# Own_18650_Board_v1_3_Final_AR.net
KiCad netlist of a schematic drawn in EAGLE
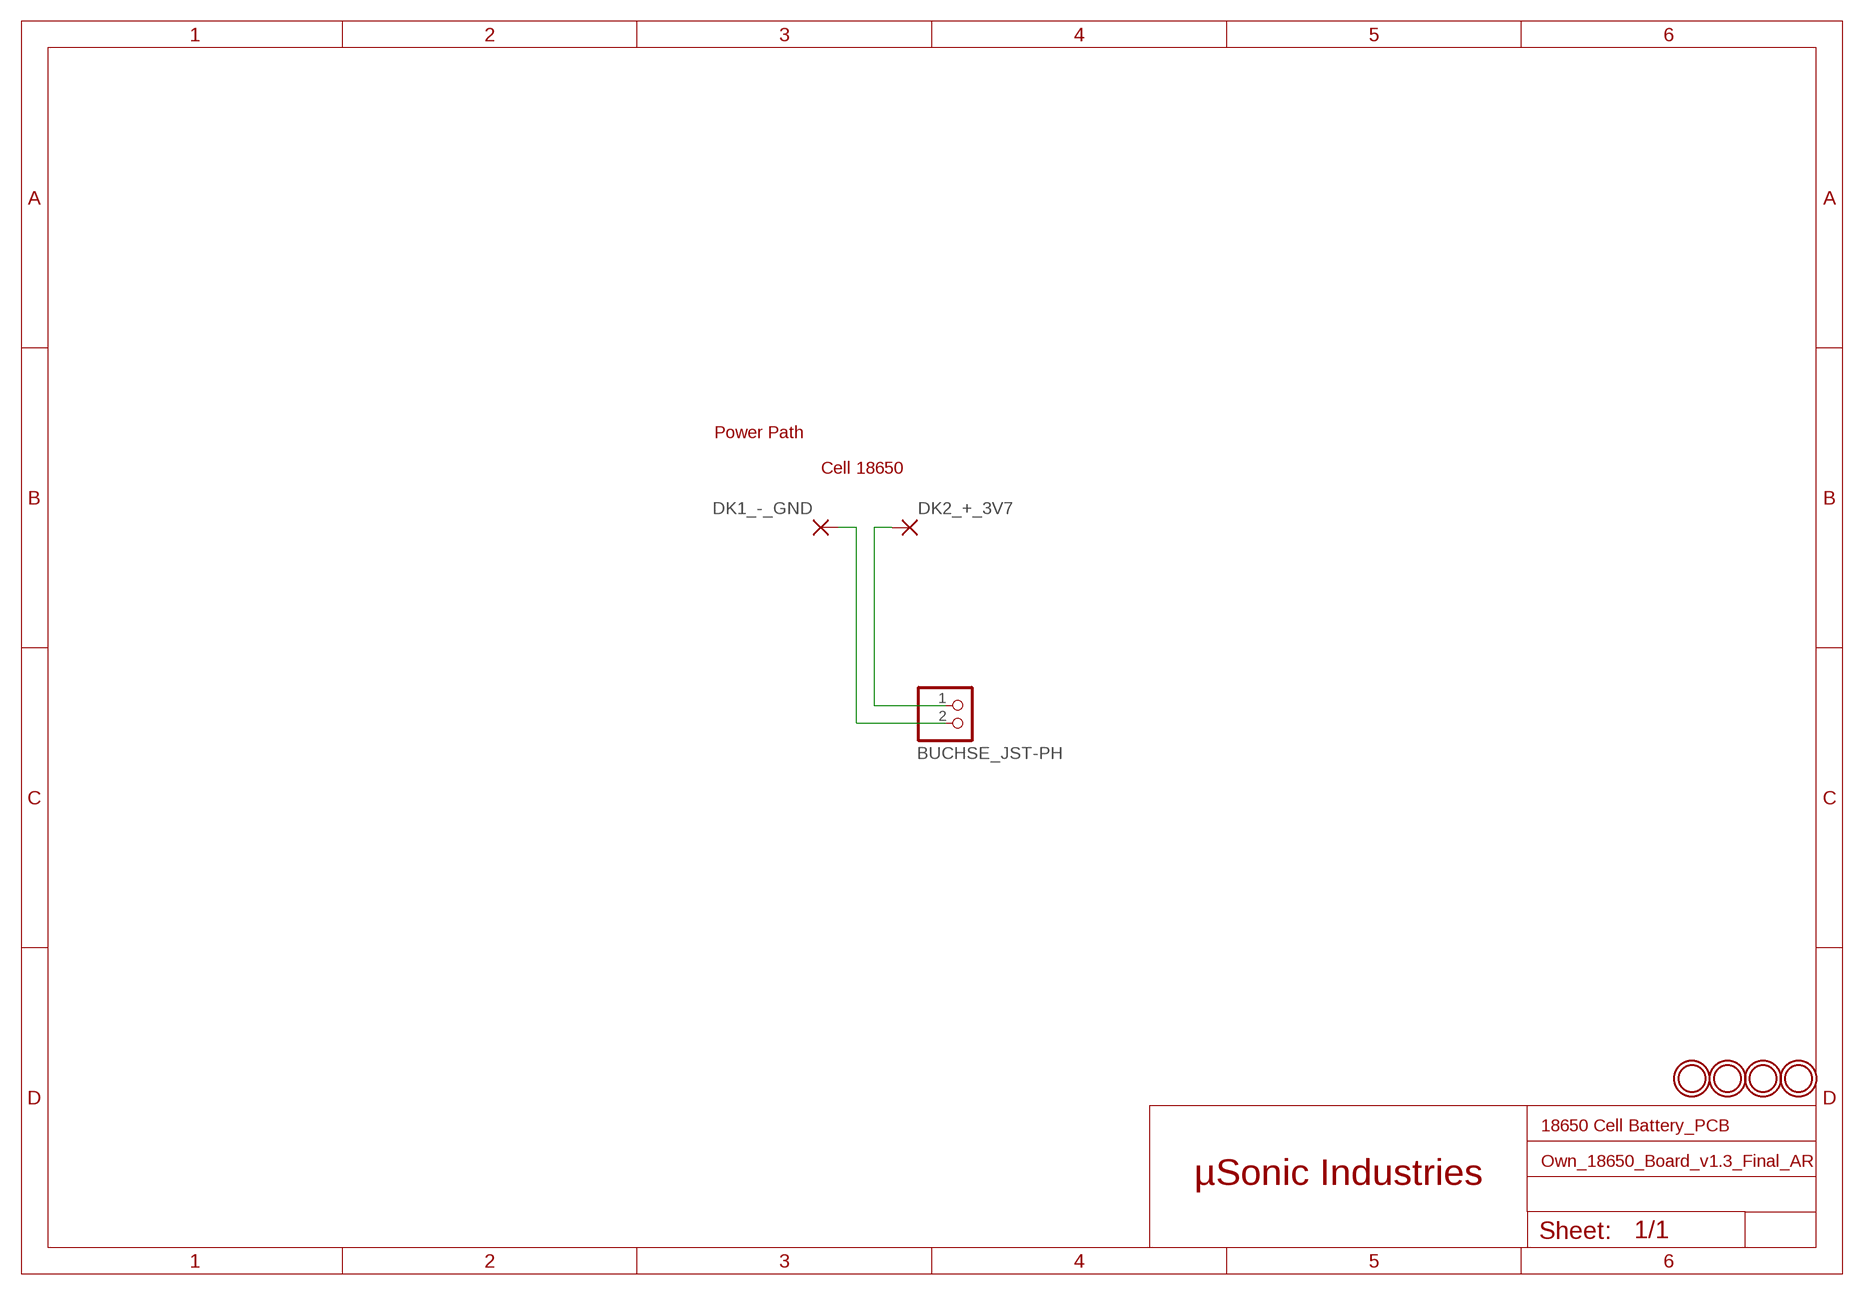
[diagram p0: schematic, sheet 1]

(export (version "E")
  (design (tool "Eeschema 10.0.6"))
  (components
    (comp (ref "BUCHSE_JST-PH")
      (value "JST_2PINOWN")
      (footprint "eagle-import:JST-PH-2-THMOWN")
      (libsource (lib "eagle-import") (part "JST_2PINOWN"))
    )
    (comp (ref "DK1_-_GND")
      (value "3,17/1,3")
      (footprint "eagle-import:3,17_1,3")
      (libsource (lib "eagle-import") (part "3,17/1,3"))
    )
    (comp (ref "DK2_+_3V7")
      (value "3,17/1,3")
      (footprint "eagle-import:3,17_1,3")
      (libsource (lib "eagle-import") (part "3,17/1,3"))
    )
    (comp (ref "U$1")
      (value "MOUNTINGHOLE2.5")
      (footprint "eagle-import:MOUNTINGHOLE_2.5_PLATED")
      (libsource (lib "eagle-import") (part "MOUNTINGHOLE2.5"))
    )
    (comp (ref "U$2")
      (value "MOUNTINGHOLE2.5")
      (footprint "eagle-import:MOUNTINGHOLE_2.5_PLATED")
      (libsource (lib "eagle-import") (part "MOUNTINGHOLE2.5"))
    )
    (comp (ref "U$3")
      (value "MOUNTINGHOLE2.5")
      (footprint "eagle-import:MOUNTINGHOLE_2.5_PLATED")
      (libsource (lib "eagle-import") (part "MOUNTINGHOLE2.5"))
    )
    (comp (ref "U$5")
      (value "MOUNTINGHOLE2.5")
      (footprint "eagle-import:MOUNTINGHOLE_2.5_PLATED")
      (libsource (lib "eagle-import") (part "MOUNTINGHOLE2.5"))
    )
  )
  (nets
    (net (code "1") (name "Net-(BUCHSE_JST-PH-1)") (class "Default")
      (node (ref "BUCHSE_JST-PH") (pin "2") (pinfunction "1_2") (pintype "passive"))
      (node (ref "DK1_-_GND") (pin "1") (pinfunction "P_1") (pintype "passive"))
    )
    (net (code "2") (name "Net-(BUCHSE_JST-PH-2)") (class "Default")
      (node (ref "BUCHSE_JST-PH") (pin "1") (pinfunction "2_1") (pintype "passive"))
      (node (ref "DK2_+_3V7") (pin "1") (pinfunction "P_1") (pintype "passive"))
    )
  )
)
